# RP_ComputeModule3_rev_3_0_USB.net
KiCad netlist of a schematic drawn in Altium Designer
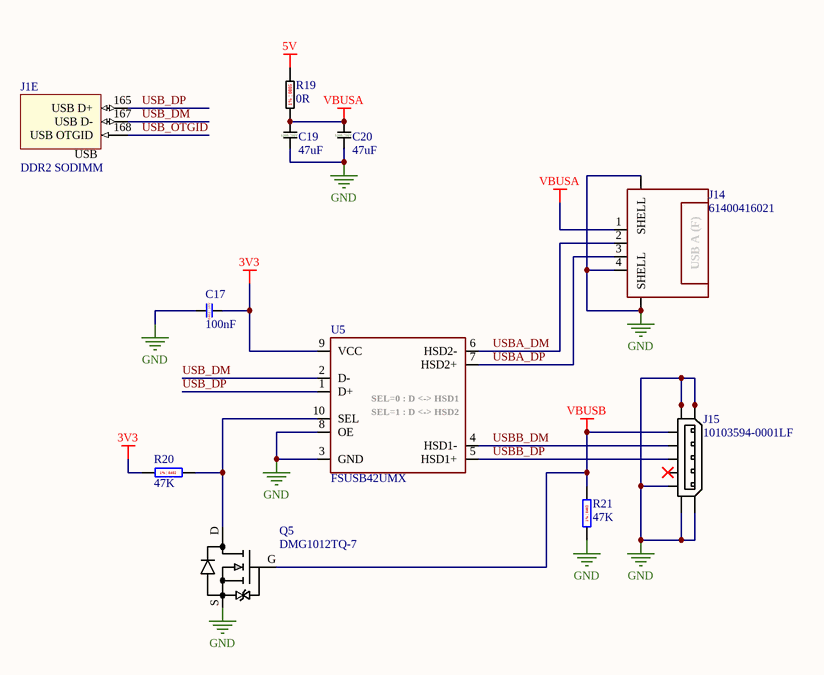
[diagram p0: RP_ComputeModule3_rev.3.0_USB.SchDoc]

(export (version "E")
  (design (tool "Eeschema 10.0.6"))
  (components
    (comp (ref "C17")
      (value "100nF")
      (footprint "GJM 0402 C")
      (description "Multilayer Ceramic Capacitors MLCC - SMD/SMT 0402 0.1uF 10volts 5%")
      (fields
        (field (name "MANUFACTURER") "Murata Electronics")
        (field (name "MANUFACTURER PART NUMBER") "GRM155R71A104JA01D")
      )
      (libsource (lib "Murata_Capacitors") (part "GRM155R71A104JA01D"))
    )
    (comp (ref "C19")
      (value "47uF")
      (footprint "MURATA C1206 / CAPC3216X94N")
      (fields
        (field (name "MANUFACTURER") "TDK")
        (field (name "MANUFACTURER PART NUMBER") "C3216JB1C476M160AB")
        (field (name "TOLERANCE") "20%")
      )
      (libsource (lib "Murata_Capacitors") (part "C3216JB1C476M160AB"))
    )
    (comp (ref "C20")
      (value "47uF")
      (footprint "MURATA C1206 / CAPC3216X94N")
      (fields
        (field (name "MANUFACTURER") "TDK")
        (field (name "MANUFACTURER PART NUMBER") "C3216JB1C476M160AB")
        (field (name "TOLERANCE") "20%")
      )
      (libsource (lib "Murata_Capacitors") (part "C3216JB1C476M160AB"))
    )
    (comp (ref "J1")
      (value "DDR2 SODIMM")
      (footprint "TE 1473005-4 (DDR2 SO-DIMM)")
      (description "TE CONNECTIVITY / AMP         1473005-4             SOCKET IC, DIMM, DDR2, 1.8V, 200WAY")
      (fields
        (field (name "MANUFACTURER") "TE Connectivity")
        (field (name "MANUFACTURER PART NUMBER") "1473005-4")
      )
      (libsource (lib "TEConnectivity_AMP") (part "1473005-4"))
    )
    (comp (ref "J14")
      (value "61400416021")
      (footprint "WE USB connector 61400416021")
      (description "USB - A USB 2.0 Receptacle Connector 4 Position Through Hole, Right Angle, Horizontal")
      (fields (field (name "MANUFACTURER") "Wurth Electronics"))
      (libsource (lib "WE_Library") (part "61400416021"))
    )
    (comp (ref "J15")
      (value "10103594-0001LF")
      (footprint "FCI_10103594-0001LF")
      (description "USB - micro B USB 2.0 Receptacle Connector 5 Position Surface Mount, Right Angle, Horizontal")
      (fields (field (name "MANUFACTURER") "Amphenol FCI"))
      (libsource (lib "Amphenol_Library") (part "10103594-0001LF"))
    )
    (comp (ref "Q5")
      (value "DMG1012TQ-7")
      (footprint "Diodes SOT523")
      (description "MOSFET NCH 20V 630MA SOT523")
      (fields (field (name "MANUFACTURER") "Diodes"))
      (libsource (lib "Diodes_Inc_Library") (part "DMG1012TQ-7"))
    )
    (comp (ref "R19")
      (value "0R")
      (footprint "YAGEO RES0402")
      (description "Thick Film Resistors - SMD 1/8W 0.0ohm 1%")
      (fields
        (field (name "MANUFACTURER") "Yageo")
        (field (name "MANUFACTURER PART NUMBER") "AC0805FR-070RL")
      )
      (libsource (lib "YAGEO_Library") (part "AC0805FR-070RL"))
    )
    (comp (ref "R20")
      (value "47K")
      (footprint "Vishay Beyschlag MCS0402")
      (description "Res Thin Film 0402 47K Ohm 1% 1/16W ±50ppm/C Molded SMD Paper T/R")
      (fields
        (field (name "MANUFACTURER") "Vishay BCcomponents")
        (field (name "MANUFACTURER PART NUMBER") "MCS04020C4702FE000")
      )
      (libsource (lib "Vishay_Library") (part "MCS04020C4702FE000"))
    )
    (comp (ref "R21")
      (value "47K")
      (footprint "Vishay Beyschlag MCS0402")
      (description "Res Thin Film 0402 47K Ohm 1% 1/16W ±50ppm/C Molded SMD Paper T/R")
      (fields
        (field (name "MANUFACTURER") "Vishay BCcomponents")
        (field (name "MANUFACTURER PART NUMBER") "MCS04020C4702FE000")
      )
      (libsource (lib "Vishay_Library") (part "MCS04020C4702FE000"))
    )
    (comp (ref "U5")
      (value "FSUSB42UMX")
      (footprint "Fairchild/OnSemi - UMLP (FSUSB42)")
      (description "Analog Switch Single DPDT 10-Pin UMLP EP T/R")
      (fields (field (name "MANUFACTURER") "ON Semiconductor / Fairchild"))
      (libsource (lib "OnSemiconductor_Library") (part "FSUSB42UMX"))
    )
  )
  (nets
    (net (code "1") (name "/USBA_DM") (class "Default")
      (node (ref "J14") (pin "2") (pinfunction "2_2") (pintype "passive"))
      (node (ref "U5") (pin "6") (pinfunction "HSD2-_6") (pintype "passive"))
    )
    (net (code "2") (name "/USBA_DP") (class "Default")
      (node (ref "J14") (pin "3") (pinfunction "3_3") (pintype "passive"))
      (node (ref "U5") (pin "7") (pinfunction "HSD2+_7") (pintype "passive"))
    )
    (net (code "3") (name "/USBB_DM") (class "Default")
      (node (ref "J15") (pin "4") (pinfunction "4_4") (pintype "passive"))
      (node (ref "U5") (pin "4") (pinfunction "HSD1-_4") (pintype "passive"))
    )
    (net (code "4") (name "/USBB_DP") (class "Default")
      (node (ref "J15") (pin "3") (pinfunction "3_3") (pintype "passive"))
      (node (ref "U5") (pin "5") (pinfunction "HSD1+_5") (pintype "passive"))
    )
    (net (code "5") (name "/USB_DM") (class "Default")
      (node (ref "J1") (pin "167") (pinfunction "USB_D-_167") (pintype "bidirectional"))
      (node (ref "U5") (pin "2") (pinfunction "D-_2") (pintype "passive"))
    )
    (net (code "6") (name "/USB_DP") (class "Default")
      (node (ref "J1") (pin "165") (pinfunction "USB_D+_165") (pintype "bidirectional"))
      (node (ref "U5") (pin "1") (pinfunction "D+_1") (pintype "passive"))
    )
    (net (code "7") (name "/USB_OTGID") (class "Default")
      (node (ref "J1") (pin "168") (pinfunction "USB_OTGID_168") (pintype "input"))
    )
    (net (code "8") (name "3V3") (class "Default")
      (node (ref "C17") (pin "1") (pinfunction "1_1") (pintype "passive"))
      (node (ref "R20") (pin "2") (pinfunction "2_2") (pintype "passive"))
      (node (ref "U5") (pin "9") (pinfunction "VCC_9") (pintype "passive"))
    )
    (net (code "9") (name "5V") (class "Default")
      (node (ref "R19") (pin "1") (pinfunction "1_1") (pintype "passive"))
    )
    (net (code "10") (name "GND") (class "Default")
      (node (ref "C17") (pin "2") (pinfunction "2_2") (pintype "passive"))
      (node (ref "C19") (pin "1") (pinfunction "1_1") (pintype "passive"))
      (node (ref "C20") (pin "1") (pinfunction "1_1") (pintype "passive"))
      (node (ref "J14") (pin "4") (pinfunction "4_4") (pintype "passive"))
      (node (ref "J14") (pin "SHELL") (pinfunction "SHELL_SHELL") (pintype "passive"))
      (node (ref "J14") (pin "SHELL2") (pinfunction "SHELL_SHELL2") (pintype "passive"))
      (node (ref "J15") (pin "1") (pinfunction "1_1") (pintype "passive"))
      (node (ref "J15") (pin "10") (pinfunction "10_10") (pintype "passive"))
      (node (ref "J15") (pin "11") (pinfunction "11_11") (pintype "passive"))
      (node (ref "J15") (pin "6") (pinfunction "6_6") (pintype "passive"))
      (node (ref "J15") (pin "7") (pinfunction "7_7") (pintype "passive"))
      (node (ref "J15") (pin "8") (pinfunction "8_8") (pintype "passive"))
      (node (ref "J15") (pin "9") (pinfunction "9_9") (pintype "passive"))
      (node (ref "Q5") (pin "S") (pinfunction "S_S") (pintype "passive"))
      (node (ref "R21") (pin "2") (pinfunction "2_2") (pintype "passive"))
      (node (ref "U5") (pin "3") (pinfunction "GND_3") (pintype "passive"))
      (node (ref "U5") (pin "8") (pinfunction "OE_8") (pintype "passive"))
    )
    (net (code "11") (name "Net-(U5-SEL)") (class "Default")
      (node (ref "Q5") (pin "D") (pinfunction "D_D") (pintype "passive"))
      (node (ref "R20") (pin "1") (pinfunction "1_1") (pintype "passive"))
      (node (ref "U5") (pin "10") (pinfunction "SEL_10") (pintype "passive"))
    )
    (net (code "12") (name "VBUSA") (class "Default")
      (node (ref "C19") (pin "2") (pinfunction "2_2") (pintype "passive"))
      (node (ref "C20") (pin "2") (pinfunction "2_2") (pintype "passive"))
      (node (ref "J14") (pin "1") (pinfunction "1_1") (pintype "passive"))
      (node (ref "R19") (pin "2") (pinfunction "2_2") (pintype "passive"))
    )
    (net (code "13") (name "VBUSB") (class "Default")
      (node (ref "J15") (pin "5") (pinfunction "5_5") (pintype "passive"))
      (node (ref "Q5") (pin "G") (pinfunction "G_G") (pintype "passive"))
      (node (ref "R21") (pin "1") (pinfunction "1_1") (pintype "passive"))
    )
    (net (code "14") (name "unconnected-(J15-Pad2)") (class "Default")
      (node (ref "J15") (pin "2") (pinfunction "2_2") (pintype "passive+no_connect"))
    )
  )
)
